# BLE-LORA-Relay-30dbm-v2_1.net
KiCad netlist of a schematic drawn in EAGLE
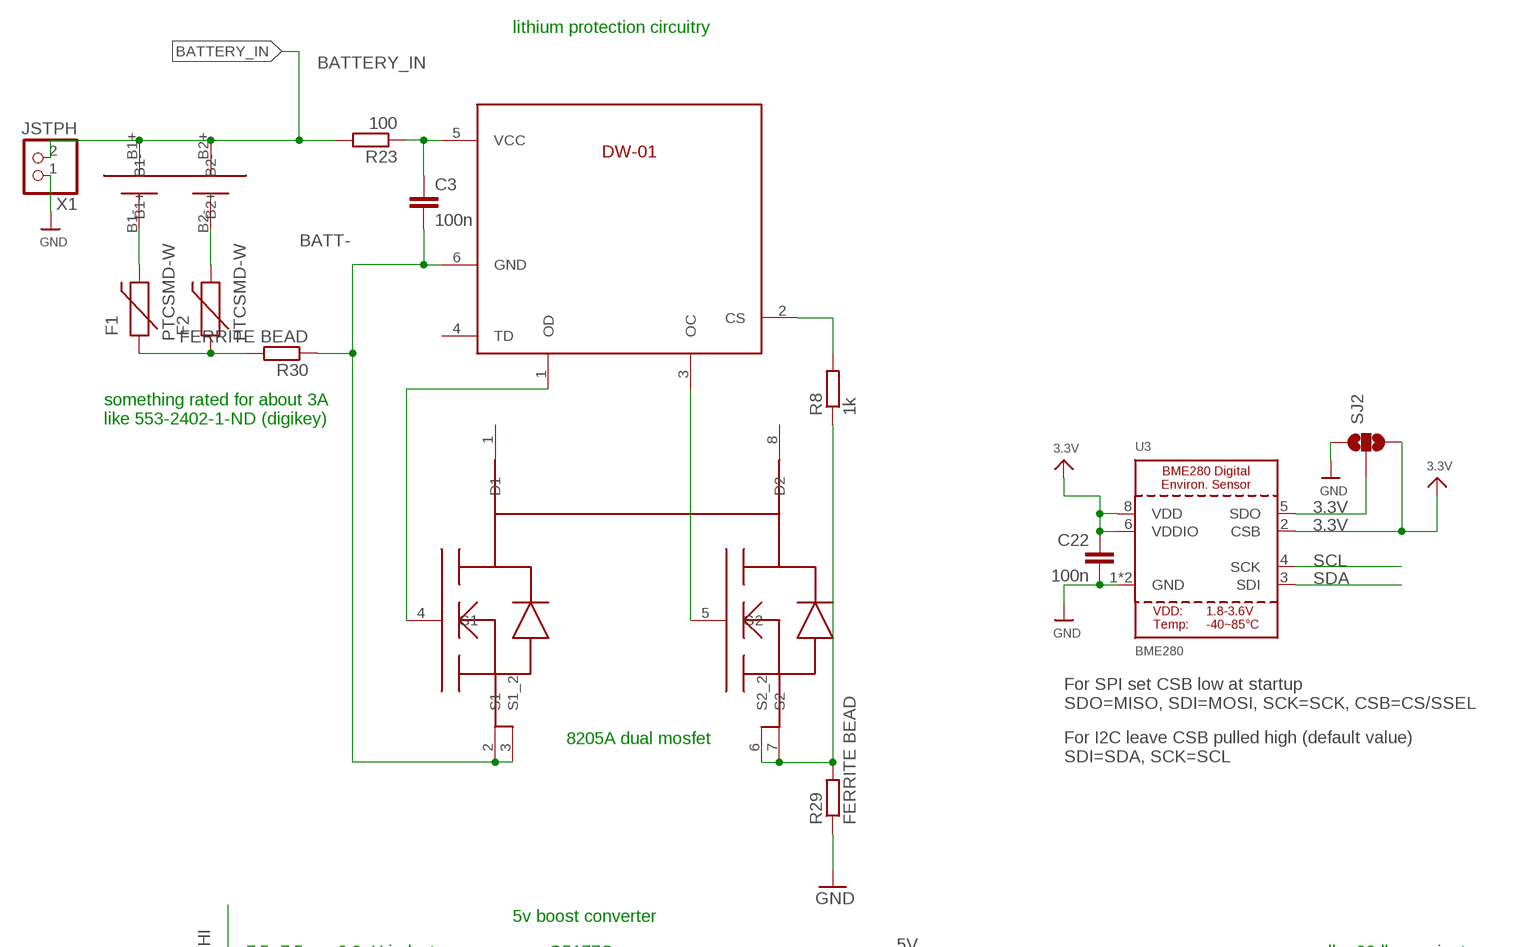
[diagram p0: schematic, sheet 1, part 1 of 3]
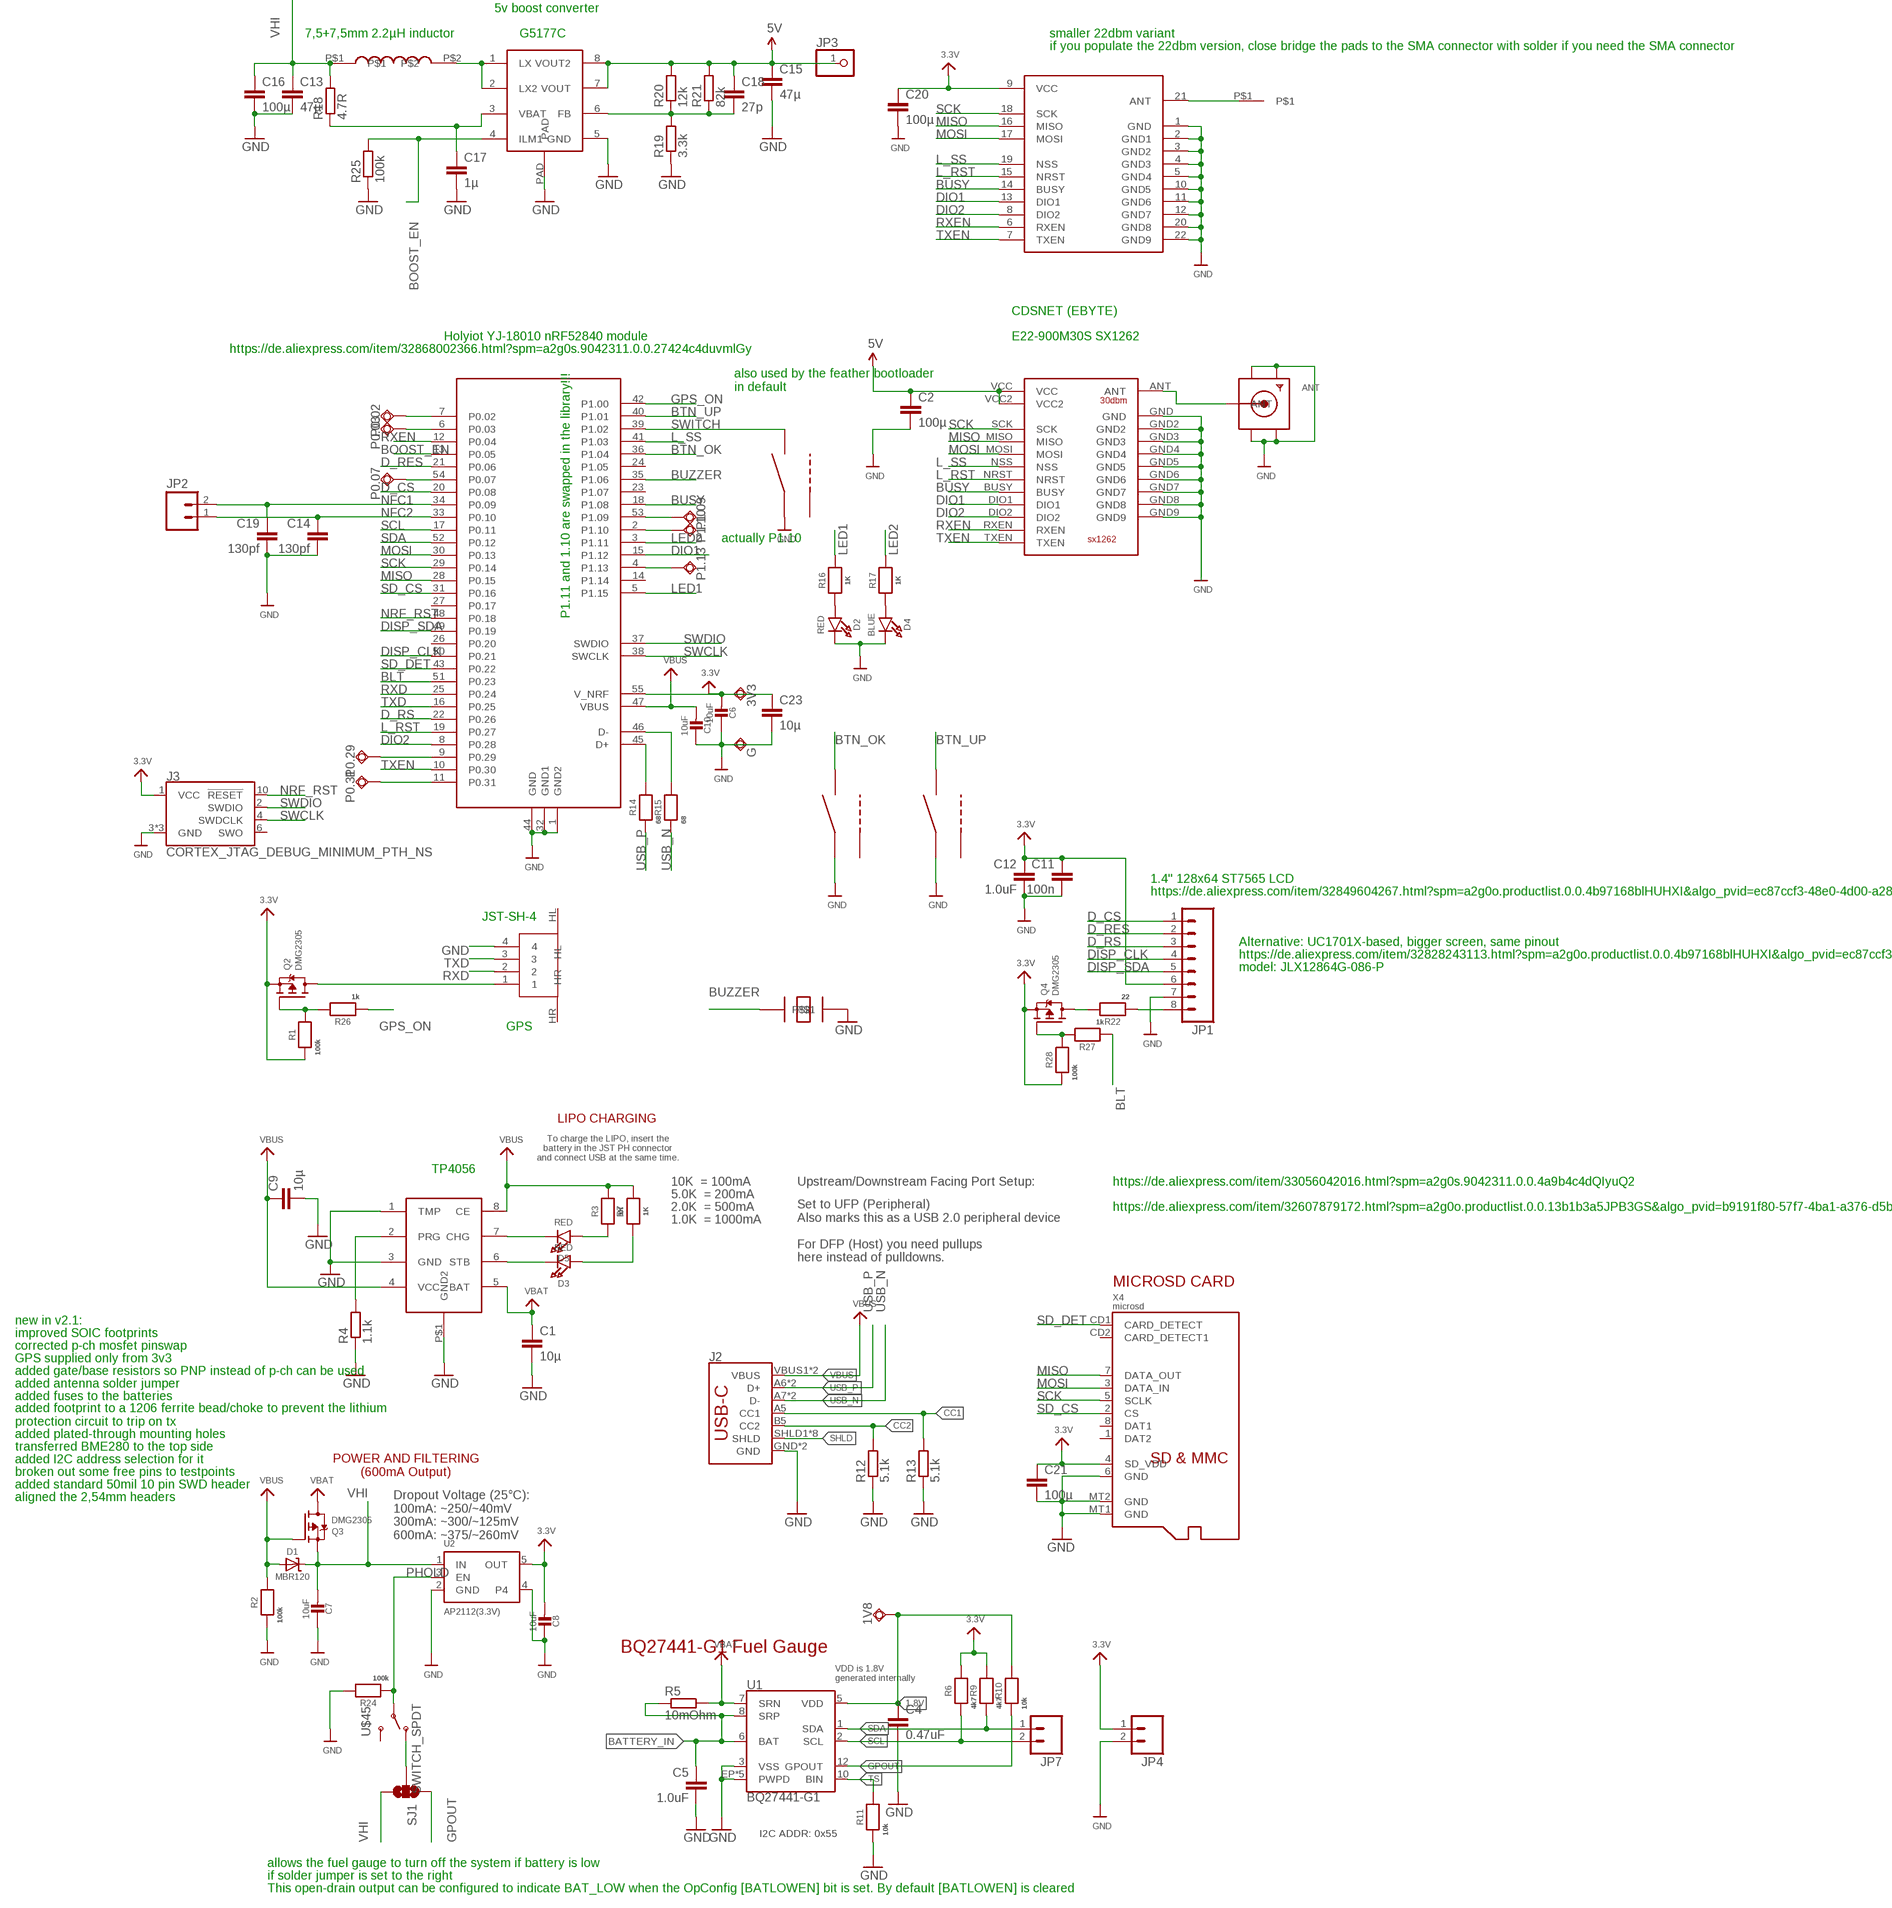
[diagram p1: schematic, sheet 1, part 2 of 3]
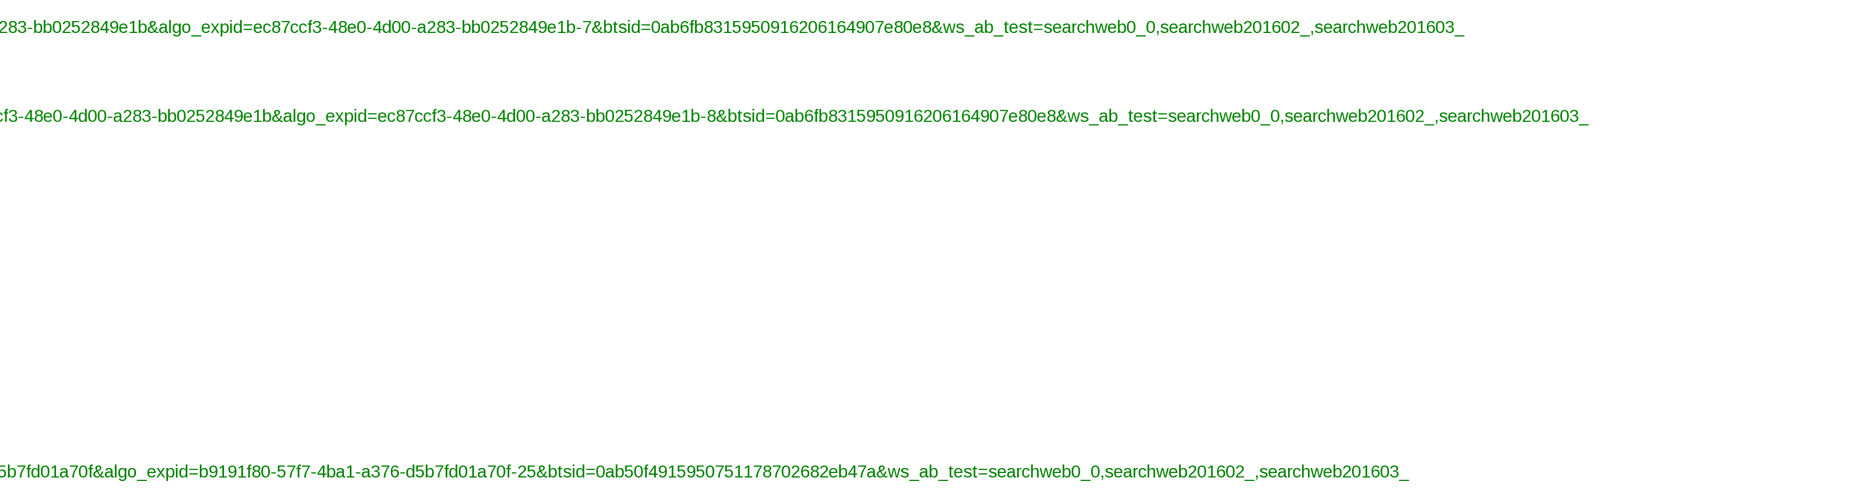
[diagram p2: schematic, sheet 1, part 3 of 3]

(export (version "E")
  (design (tool "Eeschema 10.0.6"))
  (components
    (comp (ref "1V8")
      (value "TPSQTP13R")
      (footprint "eagle-import:TP13R")
      (libsource (lib "eagle-import") (part "TPSQTP13R"))
    )
    (comp (ref "3V3")
      (value "TPSQTP13R")
      (footprint "eagle-import:TP13R")
      (libsource (lib "eagle-import") (part "TPSQTP13R"))
    )
    (comp (ref "ANT")
      (value "SMACONNECTOR_EDGE")
      (footprint "eagle-import:SMA_EDGELAUNCH")
      (libsource (lib "eagle-import") (part "SMACONNECTOR_EDGE"))
    )
    (comp (ref "C1")
      (value "10µ")
      (footprint "eagle-import:C0805")
      (libsource (lib "eagle-import") (part "C-EUC0805"))
    )
    (comp (ref "C2")
      (value "100µ")
      (footprint "eagle-import:C1206")
      (libsource (lib "eagle-import") (part "C-EUC1206"))
    )
    (comp (ref "C3")
      (value "100n")
      (footprint "eagle-import:C0603")
      (libsource (lib "eagle-import") (part "C-EUC0603"))
    )
    (comp (ref "C4")
      (value "0.47uF")
      (footprint "eagle-import:0603-CAP")
      (libsource (lib "eagle-import") (part "CAP0603-CAP"))
    )
    (comp (ref "C5")
      (value "1.0uF")
      (footprint "eagle-import:0603-CAP")
      (libsource (lib "eagle-import") (part "1.0UF-16V-10%(0603)"))
    )
    (comp (ref "C6")
      (value "10uF")
      (footprint "eagle-import:0805-NO")
      (libsource (lib "eagle-import") (part "CAP_CERAMIC0805-NOOUTLINE"))
    )
    (comp (ref "C7")
      (value "10uF")
      (footprint "eagle-import:0805-NO")
      (libsource (lib "eagle-import") (part "CAP_CERAMIC0805-NOOUTLINE"))
    )
    (comp (ref "C8")
      (value "10uF")
      (footprint "eagle-import:0805-NO")
      (libsource (lib "eagle-import") (part "CAP_CERAMIC0805-NOOUTLINE"))
    )
    (comp (ref "C9")
      (value "10µ")
      (footprint "eagle-import:C0805")
      (libsource (lib "eagle-import") (part "C-EUC0805"))
    )
    (comp (ref "C10")
      (value "10uF")
      (footprint "eagle-import:0805-NO")
      (libsource (lib "eagle-import") (part "CAP_CERAMIC0805-NOOUTLINE"))
    )
    (comp (ref "C11")
      (value "100n")
      (footprint "eagle-import:0603-CAP")
      (libsource (lib "eagle-import") (part "1.0UF-16V-10%(0603)"))
    )
    (comp (ref "C12")
      (value "1.0uF")
      (footprint "eagle-import:0603-CAP")
      (libsource (lib "eagle-import") (part "1.0UF-16V-10%(0603)"))
    )
    (comp (ref "C13")
      (value "47µ")
      (footprint "eagle-import:C0805")
      (libsource (lib "eagle-import") (part "C-EUC0805"))
    )
    (comp (ref "C14")
      (value "130pf")
      (footprint "eagle-import:0603-CAP")
      (libsource (lib "eagle-import") (part "1.0UF-16V-10%(0603)"))
    )
    (comp (ref "C15")
      (value "47µ")
      (footprint "eagle-import:C0805")
      (libsource (lib "eagle-import") (part "C-EUC0805"))
    )
    (comp (ref "C16")
      (value "100µ")
      (footprint "eagle-import:C1206")
      (libsource (lib "eagle-import") (part "C-EUC1206"))
    )
    (comp (ref "C17")
      (value "1µ")
      (footprint "eagle-import:C0603")
      (libsource (lib "eagle-import") (part "C-EUC0603"))
    )
    (comp (ref "C18")
      (value "27p")
      (footprint "eagle-import:C0603")
      (libsource (lib "eagle-import") (part "C-EUC0603"))
    )
    (comp (ref "C19")
      (value "130pf")
      (footprint "eagle-import:0603-CAP")
      (libsource (lib "eagle-import") (part "1.0UF-16V-10%(0603)"))
    )
    (comp (ref "C20")
      (value "100µ")
      (footprint "eagle-import:C1206")
      (libsource (lib "eagle-import") (part "C-EUC1206"))
    )
    (comp (ref "C21")
      (value "100µ")
      (footprint "eagle-import:C1206")
      (libsource (lib "eagle-import") (part "C-EUC1206"))
    )
    (comp (ref "C22")
      (value "100n")
      (footprint "eagle-import:0603-CAP")
      (libsource (lib "eagle-import") (part "1.0UF-16V-10%(0603)"))
    )
    (comp (ref "C23")
      (value "10µ")
      (footprint "eagle-import:C0805")
      (libsource (lib "eagle-import") (part "C-EUC0805"))
    )
    (comp (ref "D1")
      (value "MBR120")
      (footprint "eagle-import:SOD-123")
      (libsource (lib "eagle-import") (part "DIODE-SCHOTTKYSOD-123"))
    )
    (comp (ref "D2")
      (value "RED")
      (footprint "eagle-import:CHIPLED_0805_NOOUTLINE")
      (libsource (lib "eagle-import") (part "LED0805_NOOUTLINE"))
    )
    (comp (ref "D3")
      (value "RED")
      (footprint "eagle-import:CHIPLED_0805_NOOUTLINE")
      (libsource (lib "eagle-import") (part "LED0805_NOOUTLINE"))
    )
    (comp (ref "D4")
      (value "BLUE")
      (footprint "eagle-import:CHIPLED_0805_NOOUTLINE")
      (libsource (lib "eagle-import") (part "LED0805_NOOUTLINE"))
    )
    (comp (ref "D5")
      (value "RED")
      (footprint "eagle-import:CHIPLED_0805_NOOUTLINE")
      (libsource (lib "eagle-import") (part "LED0805_NOOUTLINE"))
    )
    (comp (ref "DWN")
      (value "LS12T2")
      (footprint "eagle-import:LS12T2")
      (libsource (lib "eagle-import") (part "LS12T2"))
    )
    (comp (ref "DWN1")
      (value "LS12T2")
      (footprint "eagle-import:LS12T2")
      (libsource (lib "eagle-import") (part "LS12T2"))
    )
    (comp (ref "DWN2")
      (value "LS12T2")
      (footprint "eagle-import:LS12T2")
      (libsource (lib "eagle-import") (part "LS12T2"))
    )
    (comp (ref "F1")
      (value "PTCSMD-W")
      (footprint "eagle-import:PTC-1206-WIDE")
      (libsource (lib "eagle-import") (part "PTCSMD-W"))
    )
    (comp (ref "F2")
      (value "PTCSMD-W")
      (footprint "eagle-import:PTC-1206-WIDE")
      (libsource (lib "eagle-import") (part "PTCSMD-W"))
    )
    (comp (ref "G")
      (value "TPSQTP13R")
      (footprint "eagle-import:TP13R")
      (libsource (lib "eagle-import") (part "TPSQTP13R"))
    )
    (comp (ref "J2")
      (value "USB_C16PIN")
      (footprint "eagle-import:USB-C-16P")
      (libsource (lib "eagle-import") (part "USB_C16PIN"))
    )
    (comp (ref "J3")
      (value "CORTEX_JTAG_DEBUG_MINIMUM_PTH_NS")
      (footprint "eagle-import:2X5-PTH-1.27MM-NO_SILK")
      (libsource (lib "eagle-import") (part "CORTEX_JTAG_DEBUG_MINIMUM_PTH_NS"))
    )
    (comp (ref "JP1")
      (value "M08")
      (footprint "eagle-import:1X08_ROUND")
      (libsource (lib "eagle-import") (part "M08"))
    )
    (comp (ref "JP2")
      (value "M02PTH")
      (footprint "eagle-import:1X02")
      (libsource (lib "eagle-import") (part "M02PTH"))
    )
    (comp (ref "JP3")
      (value "PINHD-1X1")
      (footprint "eagle-import:1X01")
      (libsource (lib "eagle-import") (part "PINHD-1X1"))
    )
    (comp (ref "JP4")
      (value "M02PTH")
      (footprint "eagle-import:1X02")
      (libsource (lib "eagle-import") (part "M02PTH"))
    )
    (comp (ref "JP7")
      (value "M02PTH")
      (footprint "eagle-import:1X02")
      (libsource (lib "eagle-import") (part "M02PTH"))
    )
    (comp (ref "P0.02")
      (value "TPSQTP13R")
      (footprint "eagle-import:TP13R")
      (libsource (lib "eagle-import") (part "TPSQTP13R"))
    )
    (comp (ref "P0.03")
      (value "TPSQTP13R")
      (footprint "eagle-import:TP13R")
      (libsource (lib "eagle-import") (part "TPSQTP13R"))
    )
    (comp (ref "P0.07")
      (value "TPSQTP13R")
      (footprint "eagle-import:TP13R")
      (libsource (lib "eagle-import") (part "TPSQTP13R"))
    )
    (comp (ref "P0.29")
      (value "TPSQTP13R")
      (footprint "eagle-import:TP13R")
      (libsource (lib "eagle-import") (part "TPSQTP13R"))
    )
    (comp (ref "P0.31")
      (value "TPSQTP13R")
      (footprint "eagle-import:TP13R")
      (libsource (lib "eagle-import") (part "TPSQTP13R"))
    )
    (comp (ref "P1.09")
      (value "TPSQTP13R")
      (footprint "eagle-import:TP13R")
      (libsource (lib "eagle-import") (part "TPSQTP13R"))
    )
    (comp (ref "P1.10")
      (value "TPSQTP13R")
      (footprint "eagle-import:TP13R")
      (libsource (lib "eagle-import") (part "TPSQTP13R"))
    )
    (comp (ref "P1.13")
      (value "TPSQTP13R")
      (footprint "eagle-import:TP13R")
      (libsource (lib "eagle-import") (part "TPSQTP13R"))
    )
    (comp (ref "Q2")
      (value "DMG2305")
      (footprint "eagle-import:SOT23-R")
      (libsource (lib "eagle-import") (part "MOSFET-P"))
    )
    (comp (ref "Q3")
      (value "DMG2305")
      (footprint "eagle-import:SOT23-R")
      (libsource (lib "eagle-import") (part "MOSFET-P"))
    )
    (comp (ref "Q4")
      (value "DMG2305")
      (footprint "eagle-import:SOT23-R")
      (libsource (lib "eagle-import") (part "MOSFET-P"))
    )
    (comp (ref "R1")
      (value "100k")
      (footprint "eagle-import:0603-NO")
      (libsource (lib "eagle-import") (part "RESISTOR_0603_NOOUT"))
    )
    (comp (ref "R2")
      (value "100k")
      (footprint "eagle-import:0603-NO")
      (libsource (lib "eagle-import") (part "RESISTOR_0603_NOOUT"))
    )
    (comp (ref "R3")
      (value "1K")
      (footprint "eagle-import:0603-NO")
      (libsource (lib "eagle-import") (part "RESISTOR_0603_NOOUT"))
    )
    (comp (ref "R4")
      (value "1.1k")
      (footprint "eagle-import:R0603")
      (libsource (lib "eagle-import") (part "rcl_334_R-EU_R0603"))
    )
    (comp (ref "R5")
      (value "10mOhm")
      (footprint "eagle-import:R0805")
      (libsource (lib "eagle-import") (part "rcl_334_R-EU_R0805"))
    )
    (comp (ref "R6")
      (value "4k7")
      (footprint "eagle-import:0603-NO")
      (libsource (lib "eagle-import") (part "RESISTOR_0603_NOOUT"))
    )
    (comp (ref "R7")
      (value "1K")
      (footprint "eagle-import:0603-NO")
      (libsource (lib "eagle-import") (part "RESISTOR_0603_NOOUT"))
    )
    (comp (ref "R8")
      (value "1k")
      (footprint "eagle-import:R0603")
      (libsource (lib "eagle-import") (part "rcl_334_R-EU_R0603"))
    )
    (comp (ref "R9")
      (value "4k7")
      (footprint "eagle-import:0603-NO")
      (libsource (lib "eagle-import") (part "RESISTOR_0603_NOOUT"))
    )
    (comp (ref "R10")
      (value "10k")
      (footprint "eagle-import:0603-NO")
      (libsource (lib "eagle-import") (part "RESISTOR_0603_NOOUT"))
    )
    (comp (ref "R11")
      (value "10k")
      (footprint "eagle-import:0603-NO")
      (libsource (lib "eagle-import") (part "RESISTOR_0603_NOOUT"))
    )
    (comp (ref "R12")
      (value "5.1k")
      (footprint "eagle-import:R0603")
      (libsource (lib "eagle-import") (part "rcl_334_R-EU_R0603"))
    )
    (comp (ref "R13")
      (value "5.1k")
      (footprint "eagle-import:R0603")
      (libsource (lib "eagle-import") (part "rcl_334_R-EU_R0603"))
    )
    (comp (ref "R14")
      (value "68")
      (footprint "eagle-import:0603-NO")
      (libsource (lib "eagle-import") (part "RESISTOR_0603_NOOUT"))
    )
    (comp (ref "R15")
      (value "68")
      (footprint "eagle-import:0603-NO")
      (libsource (lib "eagle-import") (part "RESISTOR_0603_NOOUT"))
    )
    (comp (ref "R16")
      (value "1K")
      (footprint "eagle-import:0603-NO")
      (libsource (lib "eagle-import") (part "RESISTOR_0603_NOOUT"))
    )
    (comp (ref "R17")
      (value "1K")
      (footprint "eagle-import:0603-NO")
      (libsource (lib "eagle-import") (part "RESISTOR_0603_NOOUT"))
    )
    (comp (ref "R18")
      (value "4.7R")
      (footprint "eagle-import:R0603")
      (libsource (lib "eagle-import") (part "rcl_334_R-EU_R0603"))
    )
    (comp (ref "R19")
      (value "3.3k")
      (footprint "eagle-import:R0603")
      (libsource (lib "eagle-import") (part "rcl_334_R-EU_R0603"))
    )
    (comp (ref "R20")
      (value "12k")
      (footprint "eagle-import:R0603")
      (libsource (lib "eagle-import") (part "rcl_334_R-EU_R0603"))
    )
    (comp (ref "R21")
      (value "82k")
      (footprint "eagle-import:R0603")
      (libsource (lib "eagle-import") (part "rcl_334_R-EU_R0603"))
    )
    (comp (ref "R22")
      (value "22")
      (footprint "eagle-import:0603-NO")
      (libsource (lib "eagle-import") (part "RESISTOR_0603_NOOUT"))
    )
    (comp (ref "R23")
      (value "100")
      (footprint "eagle-import:R0603")
      (libsource (lib "eagle-import") (part "rcl_334_R-EU_R0603"))
    )
    (comp (ref "R24")
      (value "100k")
      (footprint "eagle-import:0603-NO")
      (libsource (lib "eagle-import") (part "RESISTOR_0603_NOOUT"))
    )
    (comp (ref "R25")
      (value "100k")
      (footprint "eagle-import:R0603")
      (libsource (lib "eagle-import") (part "rcl_334_R-EU_R0603"))
    )
    (comp (ref "R26")
      (value "1k")
      (footprint "eagle-import:0603-NO")
      (libsource (lib "eagle-import") (part "RESISTOR_0603_NOOUT"))
    )
    (comp (ref "R27")
      (value "1k")
      (footprint "eagle-import:0603-NO")
      (libsource (lib "eagle-import") (part "RESISTOR_0603_NOOUT"))
    )
    (comp (ref "R28")
      (value "100k")
      (footprint "eagle-import:0603-NO")
      (libsource (lib "eagle-import") (part "RESISTOR_0603_NOOUT"))
    )
    (comp (ref "R29")
      (value "FERRITE BEAD")
      (footprint "eagle-import:R1206")
      (libsource (lib "eagle-import") (part "R-EU_R1206"))
    )
    (comp (ref "R30")
      (value "FERRITE BEAD")
      (footprint "eagle-import:R1206")
      (libsource (lib "eagle-import") (part "R-EU_R1206"))
    )
    (comp (ref "SJ1")
      (value "SOLDERJUMPER_2WAY-OLDS")
      (footprint "eagle-import:SJ_3")
      (libsource (lib "eagle-import") (part "SOLDERJUMPER_2WAY-OLDS"))
    )
    (comp (ref "SJ2")
      (value "SOLDERJUMPER_2WAY-OLDS")
      (footprint "eagle-import:SJ_3")
      (libsource (lib "eagle-import") (part "SOLDERJUMPER_2WAY-OLDS"))
    )
    (comp (ref "U$2")
      (value "BUZZER")
      (footprint "eagle-import:BUZZER")
      (libsource (lib "eagle-import") (part "BUZZER"))
    )
    (comp (ref "U$10")
      (value "2X18650")
      (footprint "eagle-import:2X18650")
      (libsource (lib "eagle-import") (part "2X18650"))
    )
    (comp (ref "U$14")
      (value "NRF52840")
      (footprint "eagle-import:NRF52840MOD")
      (libsource (lib "eagle-import") (part "NRF52840"))
    )
    (comp (ref "U$15")
      (value "SX1262-30DBM")
      (footprint "eagle-import:SX1262-30DBM")
      (libsource (lib "eagle-import") (part "SX1262-30DBM"))
    )
    (comp (ref "U$17")
      (value "JST-SH-3")
      (footprint "eagle-import:JST-SH-3")
      (libsource (lib "eagle-import") (part "JST-SH-3"))
    )
    (comp (ref "U$35")
      (value "7.5MM-COIL")
      (footprint "eagle-import:7.5MM_COIL")
      (libsource (lib "eagle-import") (part "7.5MM-COIL"))
    )
    (comp (ref "U$36")
      (value "SX1292-EBYTE")
      (footprint "eagle-import:SX1262_EBYTE")
      (libsource (lib "eagle-import") (part "SX1292-EBYTE"))
    )
    (comp (ref "U$38")
      (value "DW-01")
      (footprint "eagle-import:SOT23-6")
      (libsource (lib "eagle-import") (part "DW-01"))
    )
    (comp (ref "U$39")
      (value "G5177C_G5177C")
      (footprint "eagle-import:G5177C_SO-08")
      (libsource (lib "eagle-import") (part "G5177C_G5177C"))
    )
    (comp (ref "U$41")
      (value "SOLDERPAD")
      (footprint "eagle-import:SOLDERPAD")
      (libsource (lib "eagle-import") (part "SOLDERPAD"))
    )
    (comp (ref "U$45")
      (value "SWITCH_SPDT")
      (footprint "eagle-import:KPS-1290")
      (libsource (lib "eagle-import") (part "SWITCH_SPDT"))
    )
    (comp (ref "U$46")
      (value "8205A")
      (footprint "eagle-import:TSSOP8")
      (libsource (lib "eagle-import") (part "8205A"))
    )
    (comp (ref "U$47")
      (value "TP4056BETTER_TP4056")
      (footprint "eagle-import:TP4056BETTER_SO-08")
      (libsource (lib "eagle-import") (part "TP4056BETTER_TP4056"))
    )
    (comp (ref "U1")
      (value "BQ27441-G1")
      (footprint "eagle-import:PDSO-N12")
      (libsource (lib "eagle-import") (part "BQ27441-G1"))
    )
    (comp (ref "U2")
      (value "AP2112(3.3V)")
      (footprint "eagle-import:SOT23-5")
      (libsource (lib "eagle-import") (part "VREG_SOT23-5"))
    )
    (comp (ref "U3")
      (value "BME280")
      (footprint "eagle-import:BME280")
      (libsource (lib "eagle-import") (part "BME280"))
    )
    (comp (ref "X1")
      (value "JSTPH")
      (footprint "eagle-import:JSTPH2")
      (libsource (lib "eagle-import") (part "CON_JST_PH_2PIN"))
    )
    (comp (ref "X4")
      (value "microsd")
      (footprint "eagle-import:MICROSD")
      (libsource (lib "eagle-import") (part "MICROSD"))
    )
  )
  (nets
    (net (code "1") (name "/BATT-") (class "Default")
      (node (ref "C3") (pin "2") (pinfunction "2_2") (pintype "passive"))
      (node (ref "R30") (pin "1") (pinfunction "1_1") (pintype "passive"))
      (node (ref "U$38") (pin "6") (pinfunction "GND_6") (pintype "bidirectional"))
      (node (ref "U$46") (pin "2") (pinfunction "S1_2") (pintype "bidirectional"))
      (node (ref "U$46") (pin "3") (pinfunction "S1_2_3") (pintype "bidirectional"))
    )
    (net (code "2") (name "/BLT") (class "Default")
      (node (ref "R27") (pin "1") (pinfunction "1_1") (pintype "passive"))
      (node (ref "U$14") (pin "51") (pinfunction "P0.23_51") (pintype "bidirectional"))
    )
    (net (code "3") (name "/BOOST_EN") (class "Default")
      (node (ref "R25") (pin "2") (pinfunction "2_2") (pintype "passive"))
      (node (ref "U$14") (pin "13") (pinfunction "P0.05_13") (pintype "bidirectional"))
      (node (ref "U$39") (pin "4") (pinfunction "ILM1_4") (pintype "bidirectional"))
    )
    (net (code "4") (name "/BTN_OK") (class "Default")
      (node (ref "DWN") (pin "1") (pinfunction "1_1") (pintype "bidirectional"))
      (node (ref "U$14") (pin "36") (pinfunction "P1.04_36") (pintype "bidirectional"))
    )
    (net (code "5") (name "/BTN_UP") (class "Default")
      (node (ref "DWN1") (pin "1") (pinfunction "1_1") (pintype "bidirectional"))
      (node (ref "U$14") (pin "40") (pinfunction "P1.01_40") (pintype "bidirectional"))
    )
    (net (code "6") (name "/BUSY") (class "Default")
      (node (ref "U$14") (pin "18") (pinfunction "P1.08_18") (pintype "bidirectional"))
      (node (ref "U$15") (pin "BUSY") (pinfunction "BUSY_BUSY") (pintype "bidirectional"))
      (node (ref "U$36") (pin "14") (pinfunction "BUSY_14") (pintype "bidirectional"))
    )
    (net (code "7") (name "/BUZZER") (class "Default")
      (node (ref "U$14") (pin "35") (pinfunction "P1.06_35") (pintype "bidirectional"))
      (node (ref "U$2") (pin "P$1") (pinfunction "P$1_P$1") (pintype "bidirectional"))
    )
    (net (code "8") (name "/DIO1") (class "Default")
      (node (ref "U$14") (pin "15") (pinfunction "P1.12_15") (pintype "bidirectional"))
      (node (ref "U$15") (pin "DIO1") (pinfunction "DIO1_DIO1") (pintype "bidirectional"))
      (node (ref "U$36") (pin "13") (pinfunction "DIO1_13") (pintype "bidirectional"))
    )
    (net (code "9") (name "/DIO2") (class "Default")
      (node (ref "U$14") (pin "8") (pinfunction "P0.28_8") (pintype "bidirectional"))
      (node (ref "U$15") (pin "DIO2") (pinfunction "DIO2_DIO2") (pintype "bidirectional"))
      (node (ref "U$36") (pin "8") (pinfunction "DIO2_8") (pintype "bidirectional"))
    )
    (net (code "10") (name "/DISP_CLK") (class "Default")
      (node (ref "JP1") (pin "4") (pinfunction "4_4") (pintype "passive"))
      (node (ref "U$14") (pin "50") (pinfunction "P0.21_50") (pintype "bidirectional"))
    )
    (net (code "11") (name "/DISP_SDA") (class "Default")
      (node (ref "JP1") (pin "5") (pinfunction "5_5") (pintype "passive"))
      (node (ref "U$14") (pin "49") (pinfunction "P0.19_49") (pintype "bidirectional"))
    )
    (net (code "12") (name "/D_CS") (class "Default")
      (node (ref "JP1") (pin "1") (pinfunction "1_1") (pintype "passive"))
      (node (ref "U$14") (pin "20") (pinfunction "P0.08_20") (pintype "bidirectional"))
    )
    (net (code "13") (name "/D_RES") (class "Default")
      (node (ref "JP1") (pin "2") (pinfunction "2_2") (pintype "passive"))
      (node (ref "U$14") (pin "21") (pinfunction "P0.06_21") (pintype "bidirectional"))
    )
    (net (code "14") (name "/D_RS") (class "Default")
      (node (ref "JP1") (pin "3") (pinfunction "3_3") (pintype "passive"))
      (node (ref "U$14") (pin "22") (pinfunction "P0.26_22") (pintype "bidirectional"))
    )
    (net (code "15") (name "/GPS_ON") (class "Default")
      (node (ref "R26") (pin "1") (pinfunction "1_1") (pintype "passive"))
      (node (ref "U$14") (pin "42") (pinfunction "P1.00_42") (pintype "bidirectional"))
    )
    (net (code "16") (name "/LED1") (class "Default")
      (node (ref "R16") (pin "2") (pinfunction "2_2") (pintype "passive"))
      (node (ref "U$14") (pin "5") (pinfunction "P1.15_5") (pintype "bidirectional"))
    )
    (net (code "17") (name "/LED2") (class "Default")
      (node (ref "R17") (pin "2") (pinfunction "2_2") (pintype "passive"))
      (node (ref "U$14") (pin "3") (pinfunction "P1.11_3") (pintype "bidirectional"))
    )
    (net (code "18") (name "/L_RST") (class "Default")
      (node (ref "U$14") (pin "19") (pinfunction "P0.27_19") (pintype "bidirectional"))
      (node (ref "U$15") (pin "NRST") (pinfunction "NRST_NRST") (pintype "bidirectional"))
      (node (ref "U$36") (pin "15") (pinfunction "NRST_15") (pintype "bidirectional"))
    )
    (net (code "19") (name "/L_SS") (class "Default")
      (node (ref "U$14") (pin "41") (pinfunction "P1.03_41") (pintype "bidirectional"))
      (node (ref "U$15") (pin "NSS") (pinfunction "NSS_NSS") (pintype "bidirectional"))
      (node (ref "U$36") (pin "19") (pinfunction "NSS_19") (pintype "bidirectional"))
    )
    (net (code "20") (name "/MISO") (class "Default")
      (node (ref "U$14") (pin "28") (pinfunction "P0.15_28") (pintype "bidirectional"))
      (node (ref "U$15") (pin "MISO") (pinfunction "MISO_MISO") (pintype "bidirectional"))
      (node (ref "U$36") (pin "16") (pinfunction "MISO_16") (pintype "bidirectional"))
      (node (ref "X4") (pin "7") (pinfunction "DATA_OUT_7") (pintype "output"))
    )
    (net (code "21") (name "/MOSI") (class "Default")
      (node (ref "U$14") (pin "30") (pinfunction "P0.13_30") (pintype "bidirectional"))
      (node (ref "U$15") (pin "MOSI") (pinfunction "MOSI_MOSI") (pintype "bidirectional"))
      (node (ref "U$36") (pin "17") (pinfunction "MOSI_17") (pintype "bidirectional"))
      (node (ref "X4") (pin "3") (pinfunction "DATA_IN_3") (pintype "input"))
    )
    (net (code "22") (name "/NFC1") (class "Default")
      (node (ref "C19") (pin "1") (pinfunction "1_1") (pintype "passive"))
      (node (ref "JP2") (pin "2") (pinfunction "2_2") (pintype "passive"))
      (node (ref "U$14") (pin "34") (pinfunction "P0.09_34") (pintype "bidirectional"))
    )
    (net (code "23") (name "/NFC2") (class "Default")
      (node (ref "C14") (pin "1") (pinfunction "1_1") (pintype "passive"))
      (node (ref "JP2") (pin "1") (pinfunction "1_1") (pintype "passive"))
      (node (ref "U$14") (pin "33") (pinfunction "P0.10_33") (pintype "bidirectional"))
    )
    (net (code "24") (name "/NRF_RST") (class "Default")
      (node (ref "J3") (pin "10") (pinfunction "~{RESET}_10") (pintype "bidirectional"))
      (node (ref "U$14") (pin "48") (pinfunction "P0.18_48") (pintype "bidirectional"))
    )
    (net (code "25") (name "/PHOLD") (class "Default")
      (node (ref "R24") (pin "1") (pinfunction "1_1") (pintype "passive"))
      (node (ref "U$45") (pin "P") (pinfunction "P_P") (pintype "passive"))
      (node (ref "U2") (pin "3") (pinfunction "EN_3") (pintype "input"))
    )
    (net (code "26") (name "/RXD") (class "Default")
      (node (ref "U$14") (pin "25") (pinfunction "P0.24_25") (pintype "bidirectional"))
      (node (ref "U$17") (pin "2") (pinfunction "2_2") (pintype "bidirectional"))
    )
    (net (code "27") (name "/RXEN") (class "Default")
      (node (ref "U$14") (pin "12") (pinfunction "P0.04_12") (pintype "bidirectional"))
      (node (ref "U$15") (pin "RXEN") (pinfunction "RXEN_RXEN") (pintype "bidirectional"))
      (node (ref "U$36") (pin "6") (pinfunction "RXEN_6") (pintype "bidirectional"))
    )
    (net (code "28") (name "/SCK") (class "Default")
      (node (ref "U$14") (pin "29") (pinfunction "P0.14_29") (pintype "bidirectional"))
      (node (ref "U$15") (pin "SCK") (pinfunction "SCK_SCK") (pintype "bidirectional"))
      (node (ref "U$36") (pin "18") (pinfunction "SCK_18") (pintype "bidirectional"))
      (node (ref "X4") (pin "5") (pinfunction "SCLK_5") (pintype "input"))
    )
    (net (code "29") (name "/SD_CS") (class "Default")
      (node (ref "U$14") (pin "31") (pinfunction "P0.16_31") (pintype "bidirectional"))
      (node (ref "X4") (pin "2") (pinfunction "CS_2") (pintype "input"))
    )
    (net (code "30") (name "/SD_DET") (class "Default")
      (node (ref "U$14") (pin "43") (pinfunction "P0.22_43") (pintype "bidirectional"))
      (node (ref "X4") (pin "CD1") (pinfunction "CARD_DETECT_CD1") (pintype "passive"))
    )
    (net (code "31") (name "/SWCLK") (class "Default")
      (node (ref "J3") (pin "4") (pinfunction "SWDCLK_4") (pintype "bidirectional"))
      (node (ref "U$14") (pin "38") (pinfunction "SWCLK_38") (pintype "bidirectional"))
    )
    (net (code "32") (name "/SWDIO") (class "Default")
      (node (ref "J3") (pin "2") (pinfunction "SWDIO_2") (pintype "bidirectional"))
      (node (ref "U$14") (pin "37") (pinfunction "SWDIO_37") (pintype "bidirectional"))
    )
    (net (code "33") (name "/SWITCH") (class "Default")
      (node (ref "DWN2") (pin "1") (pinfunction "1_1") (pintype "bidirectional"))
      (node (ref "U$14") (pin "39") (pinfunction "P1.02_39") (pintype "bidirectional"))
    )
    (net (code "34") (name "/TXD") (class "Default")
      (node (ref "U$14") (pin "16") (pinfunction "P0.25_16") (pintype "bidirectional"))
      (node (ref "U$17") (pin "3") (pinfunction "3_3") (pintype "bidirectional"))
    )
    (net (code "35") (name "/TXEN") (class "Default")
      (node (ref "U$14") (pin "10") (pinfunction "P0.30_10") (pintype "bidirectional"))
      (node (ref "U$15") (pin "TXEN") (pinfunction "TXEN_TXEN") (pintype "bidirectional"))
      (node (ref "U$36") (pin "7") (pinfunction "TXEN_7") (pintype "bidirectional"))
    )
    (net (code "36") (name "/VHI") (class "Default")
      (node (ref "C13") (pin "1") (pinfunction "1_1") (pintype "passive"))
      (node (ref "C16") (pin "1") (pinfunction "1_1") (pintype "passive"))
      (node (ref "C7") (pin "2") (pinfunction "2_2") (pintype "passive"))
      (node (ref "D1") (pin "C") (pinfunction "C_C") (pintype "passive"))
      (node (ref "Q3") (pin "2") (pinfunction "S_2") (pintype "passive"))
      (node (ref "R18") (pin "2") (pinfunction "2_2") (pintype "passive"))
      (node (ref "SJ1") (pin "3") (pinfunction "3_3") (pintype "passive"))
      (node (ref "U$35") (pin "P$1") (pinfunction "P$1_P$1") (pintype "bidirectional"))
      (node (ref "U2") (pin "1") (pinfunction "IN_1") (pintype "power_in"))
    )
    (net (code "37") (name "1.8V") (class "Default")
      (node (ref "1V8") (pin "TP") (pinfunction "TP_TP") (pintype "input"))
      (node (ref "C4") (pin "1") (pinfunction "1_1") (pintype "passive"))
      (node (ref "R10") (pin "2") (pinfunction "2_2") (pintype "passive"))
      (node (ref "U1") (pin "5") (pinfunction "VDD_5") (pintype "bidirectional"))
    )
    (net (code "38") (name "3.3V") (class "Default")
      (node (ref "3V3") (pin "TP") (pinfunction "TP_TP") (pintype "input"))
      (node (ref "C11") (pin "1") (pinfunction "1_1") (pintype "passive"))
      (node (ref "C12") (pin "1") (pinfunction "1_1") (pintype "passive"))
      (node (ref "C20") (pin "1") (pinfunction "1_1") (pintype "passive"))
      (node (ref "C21") (pin "1") (pinfunction "1_1") (pintype "passive"))
      (node (ref "C22") (pin "1") (pinfunction "1_1") (pintype "passive"))
      (node (ref "C23") (pin "1") (pinfunction "1_1") (pintype "passive"))
      (node (ref "C6") (pin "2") (pinfunction "2_2") (pintype "passive"))
      (node (ref "C8") (pin "2") (pinfunction "2_2") (pintype "passive"))
      (node (ref "J3") (pin "1") (pinfunction "VCC_1") (pintype "bidirectional"))
      (node (ref "JP1") (pin "6") (pinfunction "6_6") (pintype "passive"))
      (node (ref "JP4") (pin "1") (pinfunction "1_1") (pintype "passive"))
      (node (ref "Q2") (pin "2") (pinfunction "S_2") (pintype "passive"))
      (node (ref "Q4") (pin "2") (pinfunction "S_2") (pintype "passive"))
      (node (ref "R1") (pin "1") (pinfunction "1_1") (pintype "passive"))
      (node (ref "R28") (pin "1") (pinfunction "1_1") (pintype "passive"))
      (node (ref "R6") (pin "2") (pinfunction "2_2") (pintype "passive"))
      (node (ref "R9") (pin "2") (pinfunction "2_2") (pintype "passive"))
      (node (ref "SJ2") (pin "3") (pinfunction "3_3") (pintype "passive"))
      (node (ref "U$14") (pin "55") (pinfunction "V_NRF_55") (pintype "bidirectional"))
      (node (ref "U$36") (pin "9") (pinfunction "VCC_9") (pintype "bidirectional"))
      (node (ref "U2") (pin "5") (pinfunction "OUT_5") (pintype "power_in"))
      (node (ref "U3") (pin "2") (pinfunction "CSB_2") (pintype "input"))
      (node (ref "U3") (pin "6") (pinfunction "VDDIO_6") (pintype "power_in"))
      (node (ref "U3") (pin "8") (pinfunction "VDD_8") (pintype "power_in"))
      (node (ref "X4") (pin "4") (pinfunction "SD_VDD_4") (pintype "power_in"))
    )
    (net (code "39") (name "5V") (class "Default")
      (node (ref "C15") (pin "1") (pinfunction "1_1") (pintype "passive"))
      (node (ref "C18") (pin "1") (pinfunction "1_1") (pintype "passive"))
      (node (ref "C2") (pin "1") (pinfunction "1_1") (pintype "passive"))
      (node (ref "JP3") (pin "1") (pinfunction "1_1") (pintype "passive"))
      (node (ref "R20") (pin "2") (pinfunction "2_2") (pintype "passive"))
      (node (ref "R21") (pin "2") (pinfunction "2_2") (pintype "passive"))
      (node (ref "U$15") (pin "VCC") (pinfunction "VCC_VCC") (pintype "bidirectional"))
      (node (ref "U$15") (pin "VCC2") (pinfunction "VCC2_VCC2") (pintype "bidirectional"))
      (node (ref "U$39") (pin "7") (pinfunction "VOUT_7") (pintype "bidirectional"))
      (node (ref "U$39") (pin "8") (pinfunction "VOUT2_8") (pintype "bidirectional"))
    )
    (net (code "40") (name "BATTERY_IN") (class "Default")
      (node (ref "C5") (pin "1") (pinfunction "1_1") (pintype "passive"))
      (node (ref "R23") (pin "2") (pinfunction "2_2") (pintype "passive"))
      (node (ref "R5") (pin "1") (pinfunction "1_1") (pintype "passive"))
      (node (ref "U$10") (pin "B1+") (pinfunction "B1+_B1+") (pintype "bidirectional"))
      (node (ref "U$10") (pin "B2+") (pinfunction "B2+_B2+") (pintype "bidirectional"))
      (node (ref "U1") (pin "6") (pinfunction "BAT_6") (pintype "bidirectional"))
      (node (ref "U1") (pin "8") (pinfunction "SRP_8") (pintype "bidirectional"))
      (node (ref "X1") (pin "2") (pinfunction "2_2") (pintype "passive"))
    )
    (net (code "41") (name "CC1") (class "Default")
      (node (ref "J2") (pin "A5") (pinfunction "CC1_A5") (pintype "bidirectional"))
      (node (ref "R13") (pin "2") (pinfunction "2_2") (pintype "passive"))
    )
    (net (code "42") (name "CC2") (class "Default")
      (node (ref "J2") (pin "B5") (pinfunction "CC2_B5") (pintype "bidirectional"))
      (node (ref "R12") (pin "2") (pinfunction "2_2") (pintype "passive"))
    )
    (net (code "43") (name "GND") (class "Default")
      (node (ref "ANT") (pin "GND@1") (pinfunction "GND4_GND@1") (pintype "power_in"))
      (node (ref "ANT") (pin "GND@2") (pinfunction "GND3_GND@2") (pintype "power_in"))
      (node (ref "ANT") (pin "GND@3") (pinfunction "GND2_GND@3") (pintype "power_in"))
      (node (ref "ANT") (pin "GND@4") (pinfunction "GND1_GND@4") (pintype "power_in"))
      (node (ref "C1") (pin "2") (pinfunction "2_2") (pintype "passive"))
      (node (ref "C10") (pin "1") (pinfunction "1_1") (pintype "passive"))
      (node (ref "C11") (pin "2") (pinfunction "2_2") (pintype "passive"))
      (node (ref "C12") (pin "2") (pinfunction "2_2") (pintype "passive"))
      (node (ref "C13") (pin "2") (pinfunction "2_2") (pintype "passive"))
      (node (ref "C14") (pin "2") (pinfunction "2_2") (pintype "passive"))
      (node (ref "C15") (pin "2") (pinfunction "2_2") (pintype "passive"))
      (node (ref "C16") (pin "2") (pinfunction "2_2") (pintype "passive"))
      (node (ref "C17") (pin "2") (pinfunction "2_2") (pintype "passive"))
      (node (ref "C19") (pin "2") (pinfunction "2_2") (pintype "passive"))
      (node (ref "C2") (pin "2") (pinfunction "2_2") (pintype "passive"))
      (node (ref "C20") (pin "2") (pinfunction "2_2") (pintype "passive"))
      (node (ref "C21") (pin "2") (pinfunction "2_2") (pintype "passive"))
      (node (ref "C22") (pin "2") (pinfunction "2_2") (pintype "passive"))
      (node (ref "C23") (pin "2") (pinfunction "2_2") (pintype "passive"))
      (node (ref "C4") (pin "2") (pinfunction "2_2") (pintype "passive"))
      (node (ref "C5") (pin "2") (pinfunction "2_2") (pintype "passive"))
      (node (ref "C6") (pin "1") (pinfunction "1_1") (pintype "passive"))
      (node (ref "C7") (pin "1") (pinfunction "1_1") (pintype "passive"))
      (node (ref "C8") (pin "1") (pinfunction "1_1") (pintype "passive"))
      (node (ref "C9") (pin "2") (pinfunction "2_2") (pintype "passive"))
      (node (ref "D2") (pin "C") (pinfunction "C_C") (pintype "passive"))
      (node (ref "D4") (pin "C") (pinfunction "C_C") (pintype "passive"))
      (node (ref "DWN") (pin "2") (pinfunction "2_2") (pintype "bidirectional"))
      (node (ref "DWN1") (pin "2") (pinfunction "2_2") (pintype "bidirectional"))
      (node (ref "DWN2") (pin "2") (pinfunction "2_2") (pintype "bidirectional"))
      (node (ref "G") (pin "TP") (pinfunction "TP_TP") (pintype "input"))
      (node (ref "J2") (pin "GND") (pinfunction "GND_GND") (pintype "bidirectional"))
      (node (ref "J2") (pin "GND2") (pinfunction "GND_GND2") (pintype "bidirectional"))
      (node (ref "J3") (pin "3") (pinfunction "GND_3") (pintype "bidirectional"))
      (node (ref "J3") (pin "5") (pinfunction "GND_5") (pintype "bidirectional"))
      (node (ref "J3") (pin "9") (pinfunction "GND_9") (pintype "bidirectional"))
      (node (ref "JP1") (pin "7") (pinfunction "7_7") (pintype "passive"))
      (node (ref "JP4") (pin "2") (pinfunction "2_2") (pintype "passive"))
      (node (ref "R11") (pin "1") (pinfunction "1_1") (pintype "passive"))
      (node (ref "R12") (pin "1") (pinfunction "1_1") (pintype "passive"))
      (node (ref "R13") (pin "1") (pinfunction "1_1") (pintype "passive"))
      (node (ref "R19") (pin "1") (pinfunction "1_1") (pintype "passive"))
      (node (ref "R2") (pin "1") (pinfunction "1_1") (pintype "passive"))
      (node (ref "R24") (pin "2") (pinfunction "2_2") (pintype "passive"))
      (node (ref "R25") (pin "1") (pinfunction "1_1") (pintype "passive"))
      (node (ref "R29") (pin "1") (pinfunction "1_1") (pintype "passive"))
      (node (ref "R4") (pin "1") (pinfunction "1_1") (pintype "passive"))
      (node (ref "SJ2") (pin "1") (pinfunction "1_1") (pintype "passive"))
      (node (ref "U$14") (pin "1") (pinfunction "GND2_1") (pintype "bidirectional"))
      (node (ref "U$14") (pin "32") (pinfunction "GND1_32") (pintype "bidirectional"))
      (node (ref "U$14") (pin "44") (pinfunction "GND_44") (pintype "bidirectional"))
      (node (ref "U$15") (pin "GND") (pinfunction "GND_GND") (pintype "bidirectional"))
      (node (ref "U$15") (pin "GND2") (pinfunction "GND2_GND2") (pintype "bidirectional"))
      (node (ref "U$15") (pin "GND3") (pinfunction "GND3_GND3") (pintype "bidirectional"))
      (node (ref "U$15") (pin "GND4") (pinfunction "GND4_GND4") (pintype "bidirectional"))
      (node (ref "U$15") (pin "GND5") (pinfunction "GND5_GND5") (pintype "bidirectional"))
      (node (ref "U$15") (pin "GND6") (pinfunction "GND6_GND6") (pintype "bidirectional"))
      (node (ref "U$15") (pin "GND7") (pinfunction "GND7_GND7") (pintype "bidirectional"))
      (node (ref "U$15") (pin "GND8") (pinfunction "GND8_GND8") (pintype "bidirectional"))
      (node (ref "U$15") (pin "GND9") (pinfunction "GND9_GND9") (pintype "bidirectional"))
      (node (ref "U$17") (pin "4") (pinfunction "4_4") (pintype "bidirectional"))
      (node (ref "U$2") (pin "P$2") (pinfunction "P$2_P$2") (pintype "bidirectional"))
      (node (ref "U$36") (pin "1") (pinfunction "GND_1") (pintype "bidirectional"))
      (node (ref "U$36") (pin "10") (pinfunction "GND5_10") (pintype "bidirectional"))
      (node (ref "U$36") (pin "11") (pinfunction "GND6_11") (pintype "bidirectional"))
      (node (ref "U$36") (pin "12") (pinfunction "GND7_12") (pintype "bidirectional"))
      (node (ref "U$36") (pin "2") (pinfunction "GND1_2") (pintype "bidirectional"))
      (node (ref "U$36") (pin "20") (pinfunction "GND8_20") (pintype "bidirectional"))
      (node (ref "U$36") (pin "22") (pinfunction "GND9_22") (pintype "bidirectional"))
      (node (ref "U$36") (pin "3") (pinfunction "GND2_3") (pintype "bidirectional"))
      (node (ref "U$36") (pin "4") (pinfunction "GND3_4") (pintype "bidirectional"))
      (node (ref "U$36") (pin "5") (pinfunction "GND4_5") (pintype "bidirectional"))
      (node (ref "U$39") (pin "5") (pinfunction "GND_5") (pintype "bidirectional"))
      (node (ref "U$39") (pin "PAD") (pinfunction "PAD_PAD") (pintype "bidirectional"))
      (node (ref "U$47") (pin "1") (pinfunction "TMP_1") (pintype "bidirectional"))
      (node (ref "U$47") (pin "3") (pinfunction "GND_3") (pintype "bidirectional"))
      (node (ref "U$47") (pin "P$1") (pinfunction "GND2_P$1") (pintype "bidirectional"))
      (node (ref "U1") (pin "3") (pinfunction "VSS_3") (pintype "bidirectional"))
      (node (ref "U1") (pin "EP") (pinfunction "PWPD_EP") (pintype "bidirectional"))
      (node (ref "U1") (pin "EP1") (pinfunction "PWPD_EP1") (pintype "bidirectional"))
      (node (ref "U1") (pin "EP2") (pinfunction "PWPD_EP2") (pintype "bidirectional"))
      (node (ref "U1") (pin "EP3") (pinfunction "PWPD_EP3") (pintype "bidirectional"))
      (node (ref "U1") (pin "EP4") (pinfunction "PWPD_EP4") (pintype "bidirectional"))
      (node (ref "U2") (pin "2") (pinfunction "GND_2") (pintype "power_in"))
      (node (ref "U2") (pin "4") (pinfunction "P4_4") (pintype "bidirectional"))
      (node (ref "U3") (pin "1") (pinfunction "GND_1") (pintype "power_in"))
      (node (ref "U3") (pin "7") (pinfunction "GND_7") (pintype "power_in"))
      (node (ref "X1") (pin "1") (pinfunction "1_1") (pintype "passive"))
      (node (ref "X4") (pin "6") (pinfunction "GND_6") (pintype "power_in"))
      (node (ref "X4") (pin "MT1") (pinfunction "GND_MT1") (pintype "power_in"))
      (node (ref "X4") (pin "MT2") (pinfunction "GND_MT2") (pintype "power_in"))
    )
    (net (code "44") (name "GPOUT") (class "Default")
      (node (ref "R10") (pin "1") (pinfunction "1_1") (pintype "passive"))
      (node (ref "SJ1") (pin "1") (pinfunction "1_1") (pintype "passive"))
      (node (ref "U1") (pin "12") (pinfunction "GPOUT_12") (pintype "bidirectional"))
    )
    (net (code "45") (name "Net-(ANT-ANT)") (class "Default")
      (node (ref "ANT") (pin "P") (pinfunction "ANT_P") (pintype "bidirectional"))
      (node (ref "U$15") (pin "ANT") (pinfunction "ANT_ANT") (pintype "bidirectional"))
    )
    (net (code "46") (name "Net-(D2-PadA)") (class "Default")
      (node (ref "D2") (pin "A") (pinfunction "A_A") (pintype "passive"))
      (node (ref "R16") (pin "1") (pinfunction "1_1") (pintype "passive"))
    )
    (net (code "47") (name "Net-(D3-PadA)") (class "Default")
      (node (ref "D3") (pin "A") (pinfunction "A_A") (pintype "passive"))
      (node (ref "R7") (pin "1") (pinfunction "1_1") (pintype "passive"))
    )
    (net (code "48") (name "Net-(D4-PadA)") (class "Default")
      (node (ref "D4") (pin "A") (pinfunction "A_A") (pintype "passive"))
      (node (ref "R17") (pin "1") (pinfunction "1_1") (pintype "passive"))
    )
    (net (code "49") (name "Net-(D5-PadA)") (class "Default")
      (node (ref "D5") (pin "A") (pinfunction "A_A") (pintype "passive"))
      (node (ref "R3") (pin "1") (pinfunction "1_1") (pintype "passive"))
    )
    (net (code "50") (name "Net-(F1-Pad1)") (class "Default")
      (node (ref "F1") (pin "1") (pinfunction "1_1") (pintype "bidirectional"))
      (node (ref "F2") (pin "1") (pinfunction "1_1") (pintype "bidirectional"))
      (node (ref "R30") (pin "2") (pinfunction "2_2") (pintype "passive"))
    )
    (net (code "51") (name "Net-(F1-Pad2)") (class "Default")
      (node (ref "F1") (pin "2") (pinfunction "2_2") (pintype "bidirectional"))
      (node (ref "U$10") (pin "B1-") (pinfunction "B1-_B1-") (pintype "bidirectional"))
    )
    (net (code "52") (name "Net-(F2-Pad2)") (class "Default")
      (node (ref "F2") (pin "2") (pinfunction "2_2") (pintype "bidirectional"))
      (node (ref "U$10") (pin "B2-") (pinfunction "B2-_B2-") (pintype "bidirectional"))
    )
    (net (code "53") (name "Net-(JP1-Pad8)") (class "Default")
      (node (ref "JP1") (pin "8") (pinfunction "8_8") (pintype "passive"))
      (node (ref "R22") (pin "1") (pinfunction "1_1") (pintype "passive"))
    )
    (net (code "54") (name "Net-(Q2-D)") (class "Default")
      (node (ref "Q2") (pin "3") (pinfunction "D_3") (pintype "passive"))
      (node (ref "U$17") (pin "1") (pinfunction "1_1") (pintype "bidirectional"))
    )
    (net (code "55") (name "Net-(Q2-G)") (class "Default")
      (node (ref "Q2") (pin "1") (pinfunction "G_1") (pintype "passive"))
      (node (ref "R1") (pin "2") (pinfunction "2_2") (pintype "passive"))
      (node (ref "R26") (pin "2") (pinfunction "2_2") (pintype "passive"))
    )
    (net (code "56") (name "Net-(Q4-D)") (class "Default")
      (node (ref "Q4") (pin "3") (pinfunction "D_3") (pintype "passive"))
      (node (ref "R22") (pin "2") (pinfunction "2_2") (pintype "passive"))
    )
    (net (code "57") (name "Net-(Q4-G)") (class "Default")
      (node (ref "Q4") (pin "1") (pinfunction "G_1") (pintype "passive"))
      (node (ref "R27") (pin "2") (pinfunction "2_2") (pintype "passive"))
      (node (ref "R28") (pin "2") (pinfunction "2_2") (pintype "passive"))
    )
    (net (code "58") (name "Net-(SJ1-Pad2)") (class "Default")
      (node (ref "SJ1") (pin "2") (pinfunction "2_2") (pintype "passive"))
      (node (ref "U$45") (pin "O") (pinfunction "O_O") (pintype "passive"))
    )
    (net (code "59") (name "Net-(U$14-D+)") (class "Default")
      (node (ref "R14") (pin "2") (pinfunction "2_2") (pintype "passive"))
      (node (ref "U$14") (pin "45") (pinfunction "D+_45") (pintype "bidirectional"))
    )
    (net (code "60") (name "Net-(U$14-D-)") (class "Default")
      (node (ref "R15") (pin "2") (pinfunction "2_2") (pintype "passive"))
      (node (ref "U$14") (pin "46") (pinfunction "D-_46") (pintype "bidirectional"))
    )
    (net (code "61") (name "Net-(U$14-P0.02)") (class "Default")
      (node (ref "P0.02") (pin "TP") (pinfunction "TP_TP") (pintype "input"))
      (node (ref "U$14") (pin "7") (pinfunction "P0.02_7") (pintype "bidirectional"))
    )
    (net (code "62") (name "Net-(U$14-P0.03)") (class "Default")
      (node (ref "P0.03") (pin "TP") (pinfunction "TP_TP") (pintype "input"))
      (node (ref "U$14") (pin "6") (pinfunction "P0.03_6") (pintype "bidirectional"))
    )
    (net (code "63") (name "Net-(U$14-P0.07)") (class "Default")
      (node (ref "P0.07") (pin "TP") (pinfunction "TP_TP") (pintype "input"))
      (node (ref "U$14") (pin "54") (pinfunction "P0.07_54") (pintype "bidirectional"))
    )
    (net (code "64") (name "Net-(U$14-P0.29)") (class "Default")
      (node (ref "P0.29") (pin "TP") (pinfunction "TP_TP") (pintype "input"))
      (node (ref "U$14") (pin "9") (pinfunction "P0.29_9") (pintype "bidirectional"))
    )
    (net (code "65") (name "Net-(U$14-P0.31)") (class "Default")
      (node (ref "P0.31") (pin "TP") (pinfunction "TP_TP") (pintype "input"))
      (node (ref "U$14") (pin "11") (pinfunction "P0.31_11") (pintype "bidirectional"))
    )
    (net (code "66") (name "Net-(U$14-P1.09)") (class "Default")
      (node (ref "P1.09") (pin "TP") (pinfunction "TP_TP") (pintype "input"))
      (node (ref "U$14") (pin "53") (pinfunction "P1.09_53") (pintype "bidirectional"))
    )
    (net (code "67") (name "Net-(U$14-P1.10)") (class "Default")
      (node (ref "P1.10") (pin "TP") (pinfunction "TP_TP") (pintype "input"))
      (node (ref "U$14") (pin "2") (pinfunction "P1.10_2") (pintype "bidirectional"))
    )
    (net (code "68") (name "Net-(U$14-P1.13)") (class "Default")
      (node (ref "P1.13") (pin "TP") (pinfunction "TP_TP") (pintype "input"))
      (node (ref "U$14") (pin "4") (pinfunction "P1.13_4") (pintype "bidirectional"))
    )
    (net (code "69") (name "Net-(U$36-ANT)") (class "Default")
      (node (ref "U$36") (pin "21") (pinfunction "ANT_21") (pintype "bidirectional"))
      (node (ref "U$41") (pin "P$1") (pinfunction "P$1_P$1") (pintype "bidirectional"))
    )
    (net (code "70") (name "Net-(U$38-CS)") (class "Default")
      (node (ref "R8") (pin "2") (pinfunction "2_2") (pintype "passive"))
      (node (ref "U$38") (pin "2") (pinfunction "CS_2") (pintype "bidirectional"))
    )
    (net (code "71") (name "Net-(U$38-OC)") (class "Default")
      (node (ref "U$38") (pin "3") (pinfunction "OC_3") (pintype "bidirectional"))
      (node (ref "U$46") (pin "5") (pinfunction "G2_5") (pintype "bidirectional"))
    )
    (net (code "72") (name "Net-(U$38-OD)") (class "Default")
      (node (ref "U$38") (pin "1") (pinfunction "OD_1") (pintype "bidirectional"))
      (node (ref "U$46") (pin "4") (pinfunction "G1_4") (pintype "bidirectional"))
    )
    (net (code "73") (name "Net-(U$38-VCC)") (class "Default")
      (node (ref "C3") (pin "1") (pinfunction "1_1") (pintype "passive"))
      (node (ref "R23") (pin "1") (pinfunction "1_1") (pintype "passive"))
      (node (ref "U$38") (pin "5") (pinfunction "VCC_5") (pintype "bidirectional"))
    )
    (net (code "74") (name "Net-(U$39-FB)") (class "Default")
      (node (ref "C18") (pin "2") (pinfunction "2_2") (pintype "passive"))
      (node (ref "R19") (pin "2") (pinfunction "2_2") (pintype "passive"))
      (node (ref "R20") (pin "1") (pinfunction "1_1") (pintype "passive"))
      (node (ref "R21") (pin "1") (pinfunction "1_1") (pintype "passive"))
      (node (ref "U$39") (pin "6") (pinfunction "FB_6") (pintype "bidirectional"))
    )
    (net (code "75") (name "Net-(U$39-LX)") (class "Default")
      (node (ref "U$35") (pin "P$2") (pinfunction "P$2_P$2") (pintype "bidirectional"))
      (node (ref "U$39") (pin "1") (pinfunction "LX_1") (pintype "bidirectional"))
      (node (ref "U$39") (pin "2") (pinfunction "LX2_2") (pintype "bidirectional"))
    )
    (net (code "76") (name "Net-(U$39-VBAT)") (class "Default")
      (node (ref "C17") (pin "1") (pinfunction "1_1") (pintype "passive"))
      (node (ref "R18") (pin "1") (pinfunction "1_1") (pintype "passive"))
      (node (ref "U$39") (pin "3") (pinfunction "VBAT_3") (pintype "bidirectional"))
    )
    (net (code "77") (name "Net-(U$46-S2)") (class "Default")
      (node (ref "R29") (pin "2") (pinfunction "2_2") (pintype "passive"))
      (node (ref "R8") (pin "1") (pinfunction "1_1") (pintype "passive"))
      (node (ref "U$46") (pin "6") (pinfunction "S2_2_6") (pintype "bidirectional"))
      (node (ref "U$46") (pin "7") (pinfunction "S2_7") (pintype "bidirectional"))
    )
    (net (code "78") (name "Net-(U$47-CHG)") (class "Default")
      (node (ref "D5") (pin "C") (pinfunction "C_C") (pintype "passive"))
      (node (ref "U$47") (pin "7") (pinfunction "CHG_7") (pintype "bidirectional"))
    )
    (net (code "79") (name "Net-(U$47-PRG)") (class "Default")
      (node (ref "R4") (pin "2") (pinfunction "2_2") (pintype "passive"))
      (node (ref "U$47") (pin "2") (pinfunction "PRG_2") (pintype "bidirectional"))
    )
    (net (code "80") (name "Net-(U$47-STB)") (class "Default")
      (node (ref "D3") (pin "C") (pinfunction "C_C") (pintype "passive"))
      (node (ref "U$47") (pin "6") (pinfunction "STB_6") (pintype "bidirectional"))
    )
    (net (code "81") (name "Net-(U3-SDO)") (class "Default")
      (node (ref "SJ2") (pin "2") (pinfunction "2_2") (pintype "passive"))
      (node (ref "U3") (pin "5") (pinfunction "SDO_5") (pintype "output"))
    )
    (net (code "82") (name "SCL") (class "Default")
      (node (ref "JP7") (pin "2") (pinfunction "2_2") (pintype "passive"))
      (node (ref "R6") (pin "1") (pinfunction "1_1") (pintype "passive"))
      (node (ref "U$14") (pin "17") (pinfunction "P0.11_17") (pintype "bidirectional"))
      (node (ref "U1") (pin "2") (pinfunction "SCL_2") (pintype "bidirectional"))
      (node (ref "U3") (pin "4") (pinfunction "SCK_4") (pintype "input"))
    )
    (net (code "83") (name "SDA") (class "Default")
      (node (ref "JP7") (pin "1") (pinfunction "1_1") (pintype "passive"))
      (node (ref "R9") (pin "1") (pinfunction "1_1") (pintype "passive"))
      (node (ref "U$14") (pin "52") (pinfunction "P0.12_52") (pintype "bidirectional"))
      (node (ref "U1") (pin "1") (pinfunction "SDA_1") (pintype "bidirectional"))
      (node (ref "U3") (pin "3") (pinfunction "SDI_3") (pintype "input"))
    )
    (net (code "84") (name "SHLD") (class "Default")
      (node (ref "J2") (pin "SHLD1") (pinfunction "SHLD_SHLD1") (pintype "bidirectional"))
      (node (ref "J2") (pin "SHLD2") (pinfunction "SHLD_SHLD2") (pintype "bidirectional"))
      (node (ref "J2") (pin "SHLD3") (pinfunction "SHLD_SHLD3") (pintype "bidirectional"))
      (node (ref "J2") (pin "SHLD4") (pinfunction "SHLD_SHLD4") (pintype "bidirectional"))
      (node (ref "J2") (pin "SHLD5") (pinfunction "SHLD_SHLD5") (pintype "bidirectional"))
      (node (ref "J2") (pin "SHLD6") (pinfunction "SHLD_SHLD6") (pintype "bidirectional"))
      (node (ref "J2") (pin "SHLD7") (pinfunction "SHLD_SHLD7") (pintype "bidirectional"))
      (node (ref "J2") (pin "SHLD8") (pinfunction "SHLD_SHLD8") (pintype "bidirectional"))
    )
    (net (code "85") (name "TS") (class "Default")
      (node (ref "R11") (pin "2") (pinfunction "2_2") (pintype "passive"))
      (node (ref "U1") (pin "10") (pinfunction "BIN_10") (pintype "bidirectional"))
    )
    (net (code "86") (name "USB_N") (class "Default")
      (node (ref "J2") (pin "A7") (pinfunction "D-_A7") (pintype "bidirectional"))
      (node (ref "J2") (pin "B7") (pinfunction "D-_B7") (pintype "bidirectional"))
      (node (ref "R15") (pin "1") (pinfunction "1_1") (pintype "passive"))
    )
    (net (code "87") (name "USB_P") (class "Default")
      (node (ref "J2") (pin "A6") (pinfunction "D+_A6") (pintype "bidirectional"))
      (node (ref "J2") (pin "B6") (pinfunction "D+_B6") (pintype "bidirectional"))
      (node (ref "R14") (pin "1") (pinfunction "1_1") (pintype "passive"))
    )
    (net (code "88") (name "VBAT") (class "Default")
      (node (ref "C1") (pin "1") (pinfunction "1_1") (pintype "passive"))
      (node (ref "Q3") (pin "3") (pinfunction "D_3") (pintype "passive"))
      (node (ref "R5") (pin "2") (pinfunction "2_2") (pintype "passive"))
      (node (ref "U$47") (pin "5") (pinfunction "BAT_5") (pintype "bidirectional"))
      (node (ref "U1") (pin "7") (pinfunction "SRN_7") (pintype "bidirectional"))
    )
    (net (code "89") (name "VBUS") (class "Default")
      (node (ref "C10") (pin "2") (pinfunction "2_2") (pintype "passive"))
      (node (ref "C9") (pin "1") (pinfunction "1_1") (pintype "passive"))
      (node (ref "D1") (pin "A") (pinfunction "A_A") (pintype "passive"))
      (node (ref "J2") (pin "VBUS1") (pinfunction "VBUS_VBUS1") (pintype "bidirectional"))
      (node (ref "J2") (pin "VBUS2") (pinfunction "VBUS_VBUS2") (pintype "bidirectional"))
      (node (ref "Q3") (pin "1") (pinfunction "G_1") (pintype "passive"))
      (node (ref "R2") (pin "2") (pinfunction "2_2") (pintype "passive"))
      (node (ref "R3") (pin "2") (pinfunction "2_2") (pintype "passive"))
      (node (ref "R7") (pin "2") (pinfunction "2_2") (pintype "passive"))
      (node (ref "U$14") (pin "47") (pinfunction "VBUS_47") (pintype "bidirectional"))
      (node (ref "U$47") (pin "4") (pinfunction "VCC_4") (pintype "bidirectional"))
      (node (ref "U$47") (pin "8") (pinfunction "CE_8") (pintype "bidirectional"))
    )
    (net (code "90") (name "unconnected-(DWN-FRM-PadFRAME)") (class "Default")
      (node (ref "DWN") (pin "FRAME") (pinfunction "FRM_FRAME") (pintype "bidirectional"))
    )
    (net (code "91") (name "unconnected-(DWN1-FRM-PadFRAME)") (class "Default")
      (node (ref "DWN1") (pin "FRAME") (pinfunction "FRM_FRAME") (pintype "bidirectional"))
    )
    (net (code "92") (name "unconnected-(DWN2-FRM-PadFRAME)") (class "Default")
      (node (ref "DWN2") (pin "FRAME") (pinfunction "FRM_FRAME") (pintype "bidirectional"))
    )
    (net (code "93") (name "unconnected-(J3-SWO-Pad6)") (class "Default")
      (node (ref "J3") (pin "6") (pinfunction "SWO_6") (pintype "bidirectional"))
    )
    (net (code "94") (name "unconnected-(U$14-P0.17-Pad27)") (class "Default")
      (node (ref "U$14") (pin "27") (pinfunction "P0.17_27") (pintype "bidirectional"))
    )
    (net (code "95") (name "unconnected-(U$14-P0.20-Pad26)") (class "Default")
      (node (ref "U$14") (pin "26") (pinfunction "P0.20_26") (pintype "bidirectional"))
    )
    (net (code "96") (name "unconnected-(U$14-P1.05-Pad24)") (class "Default")
      (node (ref "U$14") (pin "24") (pinfunction "P1.05_24") (pintype "bidirectional"))
    )
    (net (code "97") (name "unconnected-(U$14-P1.07-Pad23)") (class "Default")
      (node (ref "U$14") (pin "23") (pinfunction "P1.07_23") (pintype "bidirectional"))
    )
    (net (code "98") (name "unconnected-(U$14-P1.14-Pad14)") (class "Default")
      (node (ref "U$14") (pin "14") (pinfunction "P1.14_14") (pintype "bidirectional"))
    )
    (net (code "99") (name "unconnected-(U$17-PadHL)") (class "Default")
      (node (ref "U$17") (pin "HL") (pinfunction "HL_HL") (pintype "bidirectional"))
    )
    (net (code "100") (name "unconnected-(U$17-PadHR)") (class "Default")
      (node (ref "U$17") (pin "HR") (pinfunction "HR_HR") (pintype "bidirectional"))
    )
    (net (code "101") (name "unconnected-(U$38-TD-Pad4)") (class "Default")
      (node (ref "U$38") (pin "4") (pinfunction "TD_4") (pintype "bidirectional"))
    )
    (net (code "102") (name "unconnected-(U$45-PadS)") (class "Default")
      (node (ref "U$45") (pin "S") (pinfunction "S_S") (pintype "passive"))
    )
    (net (code "103") (name "unconnected-(U$46-D1-Pad1)") (class "Default")
      (node (ref "U$46") (pin "1") (pinfunction "D1_1") (pintype "bidirectional"))
    )
    (net (code "104") (name "unconnected-(U$46-D2-Pad8)") (class "Default")
      (node (ref "U$46") (pin "8") (pinfunction "D2_8") (pintype "bidirectional"))
    )
    (net (code "105") (name "unconnected-(X4-CARD_DETECT1-PadCD2)") (class "Default")
      (node (ref "X4") (pin "CD2") (pinfunction "CARD_DETECT1_CD2") (pintype "passive"))
    )
    (net (code "106") (name "unconnected-(X4-DAT1-Pad8)") (class "Default")
      (node (ref "X4") (pin "8") (pinfunction "DAT1_8") (pintype "bidirectional"))
    )
    (net (code "107") (name "unconnected-(X4-DAT2-Pad1)") (class "Default")
      (node (ref "X4") (pin "1") (pinfunction "DAT2_1") (pintype "bidirectional"))
    )
  )
)
